# Sensor-Section.net
KiCad netlist of a schematic drawn in Altium Designer
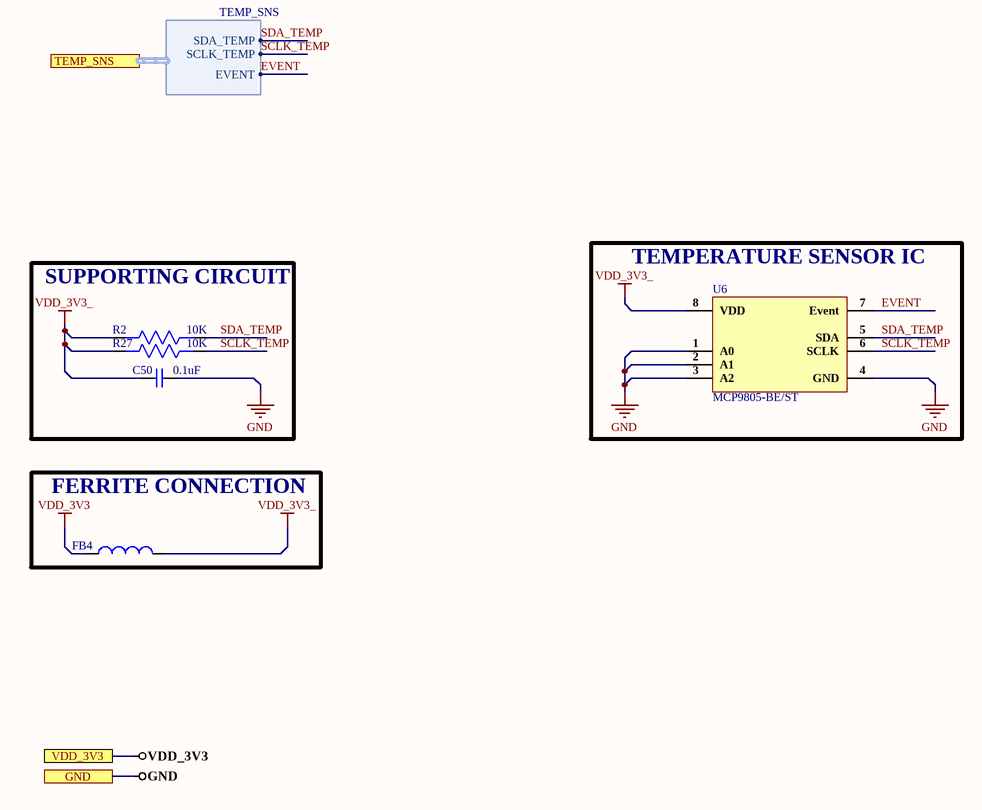
[diagram p0: Sensor-Section.SchDoc]

(export (version "E")
  (design (tool "Eeschema 10.0.6"))
  (components
    (comp (ref "C50")
      (value "0.1uF")
      (footprint "Cap0603")
      (description "Cap Ceramic 0.1uF 50VDC X7R 10% SMD 0603 Paper T/R")
      (fields
        (field (name "MANUFACTURER") "Samsung")
        (field (name "MANUFACTURER PART NUMBER") "CL10B104KB8NNNC")
      )
      (libsource (lib "Cole_Benson") (part "CL10B104KB8NNNC"))
    )
    (comp (ref "FB4")
      (value "MPZ1608S121ATDH5")
      (footprint "MPZ1608S121ATDH5")
      (description "Ferrite Beads Multi-Layer 120Ohm 25% 100MHz 2A 45mOhm DCR 0603 Automotive T/R")
      (fields (field (name "MANUFACTURER") "TDK") (field (name "TOLERANCE") "25%"))
      (libsource (lib "Cole_Benson") (part "MPZ1608S121ATDH5"))
    )
    (comp (ref "R2")
      (value "10K")
      (footprint "Res0603")
      (description "RES SMD 10K Ohm 1% 1/10W 0603")
      (fields
        (field (name "MANUFACTURER") "Yageo")
        (field (name "MANUFACTURER PART NUMBER") "RC0603FR-0710KL")
      )
      (libsource (lib "Cole_Benson") (part "RC0603FR-0710KL"))
    )
    (comp (ref "R27")
      (value "10K")
      (footprint "Res0603")
      (description "RES SMD 10K Ohm 1% 1/10W 0603")
      (fields
        (field (name "MANUFACTURER") "Yageo")
        (field (name "MANUFACTURER PART NUMBER") "RC0603FR-0710KL")
      )
      (libsource (lib "Cole_Benson") (part "RC0603FR-0710KL"))
    )
    (comp (ref "U6")
      (value "MCP9805-BE/ST")
      (footprint "8-TSSOP")
      (description "IC SENSOR THERMAL 3.0V 8TSSOP")
      (fields (field (name "MANUFACTURER") "Microchip"))
      (libsource (lib "Cole_Benson") (part "MCP9805-BE/ST"))
    )
  )
  (nets
    (net (code "2") (name "/EVENT") (class "Default")
      (node (ref "U6") (pin "7") (pinfunction "Event_7") (pintype "passive"))
    )
    (net (code "3") (name "/SCLK_TEMP") (class "Default")
      (node (ref "R27") (pin "1") (pintype "passive"))
      (node (ref "U6") (pin "6") (pinfunction "SCLK_6") (pintype "passive"))
    )
    (net (code "4") (name "/SDA_TEMP") (class "Default")
      (node (ref "R2") (pin "1") (pintype "passive"))
      (node (ref "U6") (pin "5") (pinfunction "SDA_5") (pintype "passive"))
    )
    (net (code "6") (name "GND") (class "Default")
      (node (ref "C50") (pin "2") (pinfunction "2_2") (pintype "passive"))
      (node (ref "U6") (pin "1") (pinfunction "A0_1") (pintype "passive"))
      (node (ref "U6") (pin "2") (pinfunction "A1_2") (pintype "passive"))
      (node (ref "U6") (pin "3") (pinfunction "A2_3") (pintype "passive"))
      (node (ref "U6") (pin "4") (pinfunction "GND_4") (pintype "passive"))
    )
    (net (code "7") (name "VDD_3V3") (class "Default")
      (node (ref "FB4") (pin "1") (pinfunction "1_1") (pintype "passive"))
    )
    (net (code "8") (name "VDD_3V3_") (class "Default")
      (node (ref "C50") (pin "1") (pinfunction "1_1") (pintype "passive"))
      (node (ref "FB4") (pin "2") (pinfunction "2_2") (pintype "passive"))
      (node (ref "R2") (pin "2") (pintype "passive"))
      (node (ref "R27") (pin "2") (pintype "passive"))
      (node (ref "U6") (pin "8") (pinfunction "VDD_8") (pintype "passive"))
    )
  )
)
